# Display_EveryCook.net
KiCad netlist of a schematic drawn in EAGLE
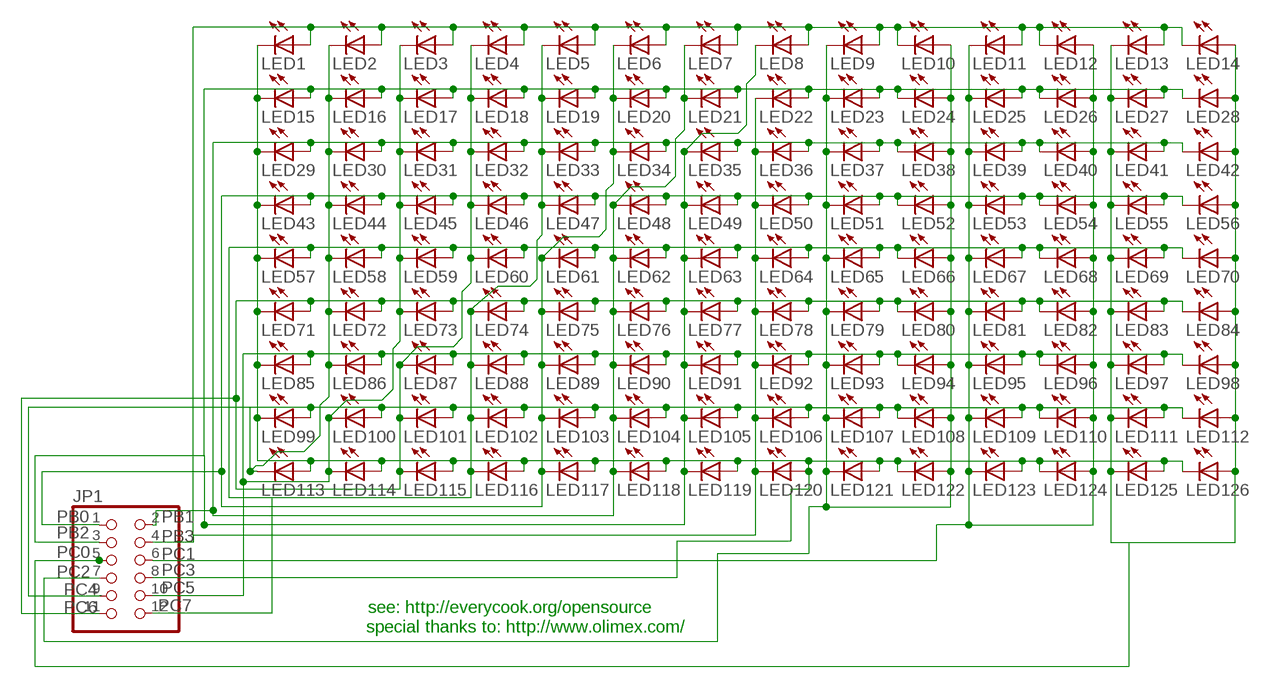
[diagram p0: schematic, sheet 1]

(export (version "E")
  (design (tool "Eeschema 10.0.6"))
  (components
    (comp (ref "JP1")
      (value "PINHD-2X6")
      (footprint "eagle-import:2X06")
      (libsource (lib "eagle-import") (part "PINHD-2X6"))
    )
    (comp (ref "LED1")
      (value "LEDKA-3528ASYC")
      (footprint "eagle-import:KA-3528ASYC")
      (libsource (lib "eagle-import") (part "LEDKA-3528ASYC"))
    )
    (comp (ref "LED2")
      (value "LEDKA-3528ASYC")
      (footprint "eagle-import:KA-3528ASYC")
      (libsource (lib "eagle-import") (part "LEDKA-3528ASYC"))
    )
    (comp (ref "LED3")
      (value "LEDKA-3528ASYC")
      (footprint "eagle-import:KA-3528ASYC")
      (libsource (lib "eagle-import") (part "LEDKA-3528ASYC"))
    )
    (comp (ref "LED4")
      (value "LEDKA-3528ASYC")
      (footprint "eagle-import:KA-3528ASYC")
      (libsource (lib "eagle-import") (part "LEDKA-3528ASYC"))
    )
    (comp (ref "LED5")
      (value "LEDKA-3528ASYC")
      (footprint "eagle-import:KA-3528ASYC")
      (libsource (lib "eagle-import") (part "LEDKA-3528ASYC"))
    )
    (comp (ref "LED6")
      (value "LEDKA-3528ASYC")
      (footprint "eagle-import:KA-3528ASYC")
      (libsource (lib "eagle-import") (part "LEDKA-3528ASYC"))
    )
    (comp (ref "LED7")
      (value "LEDKA-3528ASYC")
      (footprint "eagle-import:KA-3528ASYC")
      (libsource (lib "eagle-import") (part "LEDKA-3528ASYC"))
    )
    (comp (ref "LED8")
      (value "LEDKA-3528ASYC")
      (footprint "eagle-import:KA-3528ASYC")
      (libsource (lib "eagle-import") (part "LEDKA-3528ASYC"))
    )
    (comp (ref "LED9")
      (value "LEDKA-3528ASYC")
      (footprint "eagle-import:KA-3528ASYC")
      (libsource (lib "eagle-import") (part "LEDKA-3528ASYC"))
    )
    (comp (ref "LED10")
      (value "LEDKA-3528ASYC")
      (footprint "eagle-import:KA-3528ASYC")
      (libsource (lib "eagle-import") (part "LEDKA-3528ASYC"))
    )
    (comp (ref "LED11")
      (value "LEDKA-3528ASYC")
      (footprint "eagle-import:KA-3528ASYC")
      (libsource (lib "eagle-import") (part "LEDKA-3528ASYC"))
    )
    (comp (ref "LED12")
      (value "LEDKA-3528ASYC")
      (footprint "eagle-import:KA-3528ASYC")
      (libsource (lib "eagle-import") (part "LEDKA-3528ASYC"))
    )
    (comp (ref "LED13")
      (value "LEDKA-3528ASYC")
      (footprint "eagle-import:KA-3528ASYC")
      (libsource (lib "eagle-import") (part "LEDKA-3528ASYC"))
    )
    (comp (ref "LED14")
      (value "LEDKA-3528ASYC")
      (footprint "eagle-import:KA-3528ASYC")
      (libsource (lib "eagle-import") (part "LEDKA-3528ASYC"))
    )
    (comp (ref "LED15")
      (value "LEDKA-3528ASYC")
      (footprint "eagle-import:KA-3528ASYC")
      (libsource (lib "eagle-import") (part "LEDKA-3528ASYC"))
    )
    (comp (ref "LED16")
      (value "LEDKA-3528ASYC")
      (footprint "eagle-import:KA-3528ASYC")
      (libsource (lib "eagle-import") (part "LEDKA-3528ASYC"))
    )
    (comp (ref "LED17")
      (value "LEDKA-3528ASYC")
      (footprint "eagle-import:KA-3528ASYC")
      (libsource (lib "eagle-import") (part "LEDKA-3528ASYC"))
    )
    (comp (ref "LED18")
      (value "LEDKA-3528ASYC")
      (footprint "eagle-import:KA-3528ASYC")
      (libsource (lib "eagle-import") (part "LEDKA-3528ASYC"))
    )
    (comp (ref "LED19")
      (value "LEDKA-3528ASYC")
      (footprint "eagle-import:KA-3528ASYC")
      (libsource (lib "eagle-import") (part "LEDKA-3528ASYC"))
    )
    (comp (ref "LED20")
      (value "LEDKA-3528ASYC")
      (footprint "eagle-import:KA-3528ASYC")
      (libsource (lib "eagle-import") (part "LEDKA-3528ASYC"))
    )
    (comp (ref "LED21")
      (value "LEDKA-3528ASYC")
      (footprint "eagle-import:KA-3528ASYC")
      (libsource (lib "eagle-import") (part "LEDKA-3528ASYC"))
    )
    (comp (ref "LED22")
      (value "LEDKA-3528ASYC")
      (footprint "eagle-import:KA-3528ASYC")
      (libsource (lib "eagle-import") (part "LEDKA-3528ASYC"))
    )
    (comp (ref "LED23")
      (value "LEDKA-3528ASYC")
      (footprint "eagle-import:KA-3528ASYC")
      (libsource (lib "eagle-import") (part "LEDKA-3528ASYC"))
    )
    (comp (ref "LED24")
      (value "LEDKA-3528ASYC")
      (footprint "eagle-import:KA-3528ASYC")
      (libsource (lib "eagle-import") (part "LEDKA-3528ASYC"))
    )
    (comp (ref "LED25")
      (value "LEDKA-3528ASYC")
      (footprint "eagle-import:KA-3528ASYC")
      (libsource (lib "eagle-import") (part "LEDKA-3528ASYC"))
    )
    (comp (ref "LED26")
      (value "LEDKA-3528ASYC")
      (footprint "eagle-import:KA-3528ASYC")
      (libsource (lib "eagle-import") (part "LEDKA-3528ASYC"))
    )
    (comp (ref "LED27")
      (value "LEDKA-3528ASYC")
      (footprint "eagle-import:KA-3528ASYC")
      (libsource (lib "eagle-import") (part "LEDKA-3528ASYC"))
    )
    (comp (ref "LED28")
      (value "LEDKA-3528ASYC")
      (footprint "eagle-import:KA-3528ASYC")
      (libsource (lib "eagle-import") (part "LEDKA-3528ASYC"))
    )
    (comp (ref "LED29")
      (value "LEDKA-3528ASYC")
      (footprint "eagle-import:KA-3528ASYC")
      (libsource (lib "eagle-import") (part "LEDKA-3528ASYC"))
    )
    (comp (ref "LED30")
      (value "LEDKA-3528ASYC")
      (footprint "eagle-import:KA-3528ASYC")
      (libsource (lib "eagle-import") (part "LEDKA-3528ASYC"))
    )
    (comp (ref "LED31")
      (value "LEDKA-3528ASYC")
      (footprint "eagle-import:KA-3528ASYC")
      (libsource (lib "eagle-import") (part "LEDKA-3528ASYC"))
    )
    (comp (ref "LED32")
      (value "LEDKA-3528ASYC")
      (footprint "eagle-import:KA-3528ASYC")
      (libsource (lib "eagle-import") (part "LEDKA-3528ASYC"))
    )
    (comp (ref "LED33")
      (value "LEDKA-3528ASYC")
      (footprint "eagle-import:KA-3528ASYC")
      (libsource (lib "eagle-import") (part "LEDKA-3528ASYC"))
    )
    (comp (ref "LED34")
      (value "LEDKA-3528ASYC")
      (footprint "eagle-import:KA-3528ASYC")
      (libsource (lib "eagle-import") (part "LEDKA-3528ASYC"))
    )
    (comp (ref "LED35")
      (value "LEDKA-3528ASYC")
      (footprint "eagle-import:KA-3528ASYC")
      (libsource (lib "eagle-import") (part "LEDKA-3528ASYC"))
    )
    (comp (ref "LED36")
      (value "LEDKA-3528ASYC")
      (footprint "eagle-import:KA-3528ASYC")
      (libsource (lib "eagle-import") (part "LEDKA-3528ASYC"))
    )
    (comp (ref "LED37")
      (value "LEDKA-3528ASYC")
      (footprint "eagle-import:KA-3528ASYC")
      (libsource (lib "eagle-import") (part "LEDKA-3528ASYC"))
    )
    (comp (ref "LED38")
      (value "LEDKA-3528ASYC")
      (footprint "eagle-import:KA-3528ASYC")
      (libsource (lib "eagle-import") (part "LEDKA-3528ASYC"))
    )
    (comp (ref "LED39")
      (value "LEDKA-3528ASYC")
      (footprint "eagle-import:KA-3528ASYC")
      (libsource (lib "eagle-import") (part "LEDKA-3528ASYC"))
    )
    (comp (ref "LED40")
      (value "LEDKA-3528ASYC")
      (footprint "eagle-import:KA-3528ASYC")
      (libsource (lib "eagle-import") (part "LEDKA-3528ASYC"))
    )
    (comp (ref "LED41")
      (value "LEDKA-3528ASYC")
      (footprint "eagle-import:KA-3528ASYC")
      (libsource (lib "eagle-import") (part "LEDKA-3528ASYC"))
    )
    (comp (ref "LED42")
      (value "LEDKA-3528ASYC")
      (footprint "eagle-import:KA-3528ASYC")
      (libsource (lib "eagle-import") (part "LEDKA-3528ASYC"))
    )
    (comp (ref "LED43")
      (value "LEDKA-3528ASYC")
      (footprint "eagle-import:KA-3528ASYC")
      (libsource (lib "eagle-import") (part "LEDKA-3528ASYC"))
    )
    (comp (ref "LED44")
      (value "LEDKA-3528ASYC")
      (footprint "eagle-import:KA-3528ASYC")
      (libsource (lib "eagle-import") (part "LEDKA-3528ASYC"))
    )
    (comp (ref "LED45")
      (value "LEDKA-3528ASYC")
      (footprint "eagle-import:KA-3528ASYC")
      (libsource (lib "eagle-import") (part "LEDKA-3528ASYC"))
    )
    (comp (ref "LED46")
      (value "LEDKA-3528ASYC")
      (footprint "eagle-import:KA-3528ASYC")
      (libsource (lib "eagle-import") (part "LEDKA-3528ASYC"))
    )
    (comp (ref "LED47")
      (value "LEDKA-3528ASYC")
      (footprint "eagle-import:KA-3528ASYC")
      (libsource (lib "eagle-import") (part "LEDKA-3528ASYC"))
    )
    (comp (ref "LED48")
      (value "LEDKA-3528ASYC")
      (footprint "eagle-import:KA-3528ASYC")
      (libsource (lib "eagle-import") (part "LEDKA-3528ASYC"))
    )
    (comp (ref "LED49")
      (value "LEDKA-3528ASYC")
      (footprint "eagle-import:KA-3528ASYC")
      (libsource (lib "eagle-import") (part "LEDKA-3528ASYC"))
    )
    (comp (ref "LED50")
      (value "LEDKA-3528ASYC")
      (footprint "eagle-import:KA-3528ASYC")
      (libsource (lib "eagle-import") (part "LEDKA-3528ASYC"))
    )
    (comp (ref "LED51")
      (value "LEDKA-3528ASYC")
      (footprint "eagle-import:KA-3528ASYC")
      (libsource (lib "eagle-import") (part "LEDKA-3528ASYC"))
    )
    (comp (ref "LED52")
      (value "LEDKA-3528ASYC")
      (footprint "eagle-import:KA-3528ASYC")
      (libsource (lib "eagle-import") (part "LEDKA-3528ASYC"))
    )
    (comp (ref "LED53")
      (value "LEDKA-3528ASYC")
      (footprint "eagle-import:KA-3528ASYC")
      (libsource (lib "eagle-import") (part "LEDKA-3528ASYC"))
    )
    (comp (ref "LED54")
      (value "LEDKA-3528ASYC")
      (footprint "eagle-import:KA-3528ASYC")
      (libsource (lib "eagle-import") (part "LEDKA-3528ASYC"))
    )
    (comp (ref "LED55")
      (value "LEDKA-3528ASYC")
      (footprint "eagle-import:KA-3528ASYC")
      (libsource (lib "eagle-import") (part "LEDKA-3528ASYC"))
    )
    (comp (ref "LED56")
      (value "LEDKA-3528ASYC")
      (footprint "eagle-import:KA-3528ASYC")
      (libsource (lib "eagle-import") (part "LEDKA-3528ASYC"))
    )
    (comp (ref "LED57")
      (value "LEDKA-3528ASYC")
      (footprint "eagle-import:KA-3528ASYC")
      (libsource (lib "eagle-import") (part "LEDKA-3528ASYC"))
    )
    (comp (ref "LED58")
      (value "LEDKA-3528ASYC")
      (footprint "eagle-import:KA-3528ASYC")
      (libsource (lib "eagle-import") (part "LEDKA-3528ASYC"))
    )
    (comp (ref "LED59")
      (value "LEDKA-3528ASYC")
      (footprint "eagle-import:KA-3528ASYC")
      (libsource (lib "eagle-import") (part "LEDKA-3528ASYC"))
    )
    (comp (ref "LED60")
      (value "LEDKA-3528ASYC")
      (footprint "eagle-import:KA-3528ASYC")
      (libsource (lib "eagle-import") (part "LEDKA-3528ASYC"))
    )
    (comp (ref "LED61")
      (value "LEDKA-3528ASYC")
      (footprint "eagle-import:KA-3528ASYC")
      (libsource (lib "eagle-import") (part "LEDKA-3528ASYC"))
    )
    (comp (ref "LED62")
      (value "LEDKA-3528ASYC")
      (footprint "eagle-import:KA-3528ASYC")
      (libsource (lib "eagle-import") (part "LEDKA-3528ASYC"))
    )
    (comp (ref "LED63")
      (value "LEDKA-3528ASYC")
      (footprint "eagle-import:KA-3528ASYC")
      (libsource (lib "eagle-import") (part "LEDKA-3528ASYC"))
    )
    (comp (ref "LED64")
      (value "LEDKA-3528ASYC")
      (footprint "eagle-import:KA-3528ASYC")
      (libsource (lib "eagle-import") (part "LEDKA-3528ASYC"))
    )
    (comp (ref "LED65")
      (value "LEDKA-3528ASYC")
      (footprint "eagle-import:KA-3528ASYC")
      (libsource (lib "eagle-import") (part "LEDKA-3528ASYC"))
    )
    (comp (ref "LED66")
      (value "LEDKA-3528ASYC")
      (footprint "eagle-import:KA-3528ASYC")
      (libsource (lib "eagle-import") (part "LEDKA-3528ASYC"))
    )
    (comp (ref "LED67")
      (value "LEDKA-3528ASYC")
      (footprint "eagle-import:KA-3528ASYC")
      (libsource (lib "eagle-import") (part "LEDKA-3528ASYC"))
    )
    (comp (ref "LED68")
      (value "LEDKA-3528ASYC")
      (footprint "eagle-import:KA-3528ASYC")
      (libsource (lib "eagle-import") (part "LEDKA-3528ASYC"))
    )
    (comp (ref "LED69")
      (value "LEDKA-3528ASYC")
      (footprint "eagle-import:KA-3528ASYC")
      (libsource (lib "eagle-import") (part "LEDKA-3528ASYC"))
    )
    (comp (ref "LED70")
      (value "LEDKA-3528ASYC")
      (footprint "eagle-import:KA-3528ASYC")
      (libsource (lib "eagle-import") (part "LEDKA-3528ASYC"))
    )
    (comp (ref "LED71")
      (value "LEDKA-3528ASYC")
      (footprint "eagle-import:KA-3528ASYC")
      (libsource (lib "eagle-import") (part "LEDKA-3528ASYC"))
    )
    (comp (ref "LED72")
      (value "LEDKA-3528ASYC")
      (footprint "eagle-import:KA-3528ASYC")
      (libsource (lib "eagle-import") (part "LEDKA-3528ASYC"))
    )
    (comp (ref "LED73")
      (value "LEDKA-3528ASYC")
      (footprint "eagle-import:KA-3528ASYC")
      (libsource (lib "eagle-import") (part "LEDKA-3528ASYC"))
    )
    (comp (ref "LED74")
      (value "LEDKA-3528ASYC")
      (footprint "eagle-import:KA-3528ASYC")
      (libsource (lib "eagle-import") (part "LEDKA-3528ASYC"))
    )
    (comp (ref "LED75")
      (value "LEDKA-3528ASYC")
      (footprint "eagle-import:KA-3528ASYC")
      (libsource (lib "eagle-import") (part "LEDKA-3528ASYC"))
    )
    (comp (ref "LED76")
      (value "LEDKA-3528ASYC")
      (footprint "eagle-import:KA-3528ASYC")
      (libsource (lib "eagle-import") (part "LEDKA-3528ASYC"))
    )
    (comp (ref "LED77")
      (value "LEDKA-3528ASYC")
      (footprint "eagle-import:KA-3528ASYC")
      (libsource (lib "eagle-import") (part "LEDKA-3528ASYC"))
    )
    (comp (ref "LED78")
      (value "LEDKA-3528ASYC")
      (footprint "eagle-import:KA-3528ASYC")
      (libsource (lib "eagle-import") (part "LEDKA-3528ASYC"))
    )
    (comp (ref "LED79")
      (value "LEDKA-3528ASYC")
      (footprint "eagle-import:KA-3528ASYC")
      (libsource (lib "eagle-import") (part "LEDKA-3528ASYC"))
    )
    (comp (ref "LED80")
      (value "LEDKA-3528ASYC")
      (footprint "eagle-import:KA-3528ASYC")
      (libsource (lib "eagle-import") (part "LEDKA-3528ASYC"))
    )
    (comp (ref "LED81")
      (value "LEDKA-3528ASYC")
      (footprint "eagle-import:KA-3528ASYC")
      (libsource (lib "eagle-import") (part "LEDKA-3528ASYC"))
    )
    (comp (ref "LED82")
      (value "LEDKA-3528ASYC")
      (footprint "eagle-import:KA-3528ASYC")
      (libsource (lib "eagle-import") (part "LEDKA-3528ASYC"))
    )
    (comp (ref "LED83")
      (value "LEDKA-3528ASYC")
      (footprint "eagle-import:KA-3528ASYC")
      (libsource (lib "eagle-import") (part "LEDKA-3528ASYC"))
    )
    (comp (ref "LED84")
      (value "LEDKA-3528ASYC")
      (footprint "eagle-import:KA-3528ASYC")
      (libsource (lib "eagle-import") (part "LEDKA-3528ASYC"))
    )
    (comp (ref "LED85")
      (value "LEDKA-3528ASYC")
      (footprint "eagle-import:KA-3528ASYC")
      (libsource (lib "eagle-import") (part "LEDKA-3528ASYC"))
    )
    (comp (ref "LED86")
      (value "LEDKA-3528ASYC")
      (footprint "eagle-import:KA-3528ASYC")
      (libsource (lib "eagle-import") (part "LEDKA-3528ASYC"))
    )
    (comp (ref "LED87")
      (value "LEDKA-3528ASYC")
      (footprint "eagle-import:KA-3528ASYC")
      (libsource (lib "eagle-import") (part "LEDKA-3528ASYC"))
    )
    (comp (ref "LED88")
      (value "LEDKA-3528ASYC")
      (footprint "eagle-import:KA-3528ASYC")
      (libsource (lib "eagle-import") (part "LEDKA-3528ASYC"))
    )
    (comp (ref "LED89")
      (value "LEDKA-3528ASYC")
      (footprint "eagle-import:KA-3528ASYC")
      (libsource (lib "eagle-import") (part "LEDKA-3528ASYC"))
    )
    (comp (ref "LED90")
      (value "LEDKA-3528ASYC")
      (footprint "eagle-import:KA-3528ASYC")
      (libsource (lib "eagle-import") (part "LEDKA-3528ASYC"))
    )
    (comp (ref "LED91")
      (value "LEDKA-3528ASYC")
      (footprint "eagle-import:KA-3528ASYC")
      (libsource (lib "eagle-import") (part "LEDKA-3528ASYC"))
    )
    (comp (ref "LED92")
      (value "LEDKA-3528ASYC")
      (footprint "eagle-import:KA-3528ASYC")
      (libsource (lib "eagle-import") (part "LEDKA-3528ASYC"))
    )
    (comp (ref "LED93")
      (value "LEDKA-3528ASYC")
      (footprint "eagle-import:KA-3528ASYC")
      (libsource (lib "eagle-import") (part "LEDKA-3528ASYC"))
    )
    (comp (ref "LED94")
      (value "LEDKA-3528ASYC")
      (footprint "eagle-import:KA-3528ASYC")
      (libsource (lib "eagle-import") (part "LEDKA-3528ASYC"))
    )
    (comp (ref "LED95")
      (value "LEDKA-3528ASYC")
      (footprint "eagle-import:KA-3528ASYC")
      (libsource (lib "eagle-import") (part "LEDKA-3528ASYC"))
    )
    (comp (ref "LED96")
      (value "LEDKA-3528ASYC")
      (footprint "eagle-import:KA-3528ASYC")
      (libsource (lib "eagle-import") (part "LEDKA-3528ASYC"))
    )
    (comp (ref "LED97")
      (value "LEDKA-3528ASYC")
      (footprint "eagle-import:KA-3528ASYC")
      (libsource (lib "eagle-import") (part "LEDKA-3528ASYC"))
    )
    (comp (ref "LED98")
      (value "LEDKA-3528ASYC")
      (footprint "eagle-import:KA-3528ASYC")
      (libsource (lib "eagle-import") (part "LEDKA-3528ASYC"))
    )
    (comp (ref "LED99")
      (value "LEDKA-3528ASYC")
      (footprint "eagle-import:KA-3528ASYC")
      (libsource (lib "eagle-import") (part "LEDKA-3528ASYC"))
    )
    (comp (ref "LED100")
      (value "LEDKA-3528ASYC")
      (footprint "eagle-import:KA-3528ASYC")
      (libsource (lib "eagle-import") (part "LEDKA-3528ASYC"))
    )
    (comp (ref "LED101")
      (value "LEDKA-3528ASYC")
      (footprint "eagle-import:KA-3528ASYC")
      (libsource (lib "eagle-import") (part "LEDKA-3528ASYC"))
    )
    (comp (ref "LED102")
      (value "LEDKA-3528ASYC")
      (footprint "eagle-import:KA-3528ASYC")
      (libsource (lib "eagle-import") (part "LEDKA-3528ASYC"))
    )
    (comp (ref "LED103")
      (value "LEDKA-3528ASYC")
      (footprint "eagle-import:KA-3528ASYC")
      (libsource (lib "eagle-import") (part "LEDKA-3528ASYC"))
    )
    (comp (ref "LED104")
      (value "LEDKA-3528ASYC")
      (footprint "eagle-import:KA-3528ASYC")
      (libsource (lib "eagle-import") (part "LEDKA-3528ASYC"))
    )
    (comp (ref "LED105")
      (value "LEDKA-3528ASYC")
      (footprint "eagle-import:KA-3528ASYC")
      (libsource (lib "eagle-import") (part "LEDKA-3528ASYC"))
    )
    (comp (ref "LED106")
      (value "LEDKA-3528ASYC")
      (footprint "eagle-import:KA-3528ASYC")
      (libsource (lib "eagle-import") (part "LEDKA-3528ASYC"))
    )
    (comp (ref "LED107")
      (value "LEDKA-3528ASYC")
      (footprint "eagle-import:KA-3528ASYC")
      (libsource (lib "eagle-import") (part "LEDKA-3528ASYC"))
    )
    (comp (ref "LED108")
      (value "LEDKA-3528ASYC")
      (footprint "eagle-import:KA-3528ASYC")
      (libsource (lib "eagle-import") (part "LEDKA-3528ASYC"))
    )
    (comp (ref "LED109")
      (value "LEDKA-3528ASYC")
      (footprint "eagle-import:KA-3528ASYC")
      (libsource (lib "eagle-import") (part "LEDKA-3528ASYC"))
    )
    (comp (ref "LED110")
      (value "LEDKA-3528ASYC")
      (footprint "eagle-import:KA-3528ASYC")
      (libsource (lib "eagle-import") (part "LEDKA-3528ASYC"))
    )
    (comp (ref "LED111")
      (value "LEDKA-3528ASYC")
      (footprint "eagle-import:KA-3528ASYC")
      (libsource (lib "eagle-import") (part "LEDKA-3528ASYC"))
    )
    (comp (ref "LED112")
      (value "LEDKA-3528ASYC")
      (footprint "eagle-import:KA-3528ASYC")
      (libsource (lib "eagle-import") (part "LEDKA-3528ASYC"))
    )
    (comp (ref "LED113")
      (value "LEDKA-3528ASYC")
      (footprint "eagle-import:KA-3528ASYC")
      (libsource (lib "eagle-import") (part "LEDKA-3528ASYC"))
    )
    (comp (ref "LED114")
      (value "LEDKA-3528ASYC")
      (footprint "eagle-import:KA-3528ASYC")
      (libsource (lib "eagle-import") (part "LEDKA-3528ASYC"))
    )
    (comp (ref "LED115")
      (value "LEDKA-3528ASYC")
      (footprint "eagle-import:KA-3528ASYC")
      (libsource (lib "eagle-import") (part "LEDKA-3528ASYC"))
    )
    (comp (ref "LED116")
      (value "LEDKA-3528ASYC")
      (footprint "eagle-import:KA-3528ASYC")
      (libsource (lib "eagle-import") (part "LEDKA-3528ASYC"))
    )
    (comp (ref "LED117")
      (value "LEDKA-3528ASYC")
      (footprint "eagle-import:KA-3528ASYC")
      (libsource (lib "eagle-import") (part "LEDKA-3528ASYC"))
    )
    (comp (ref "LED118")
      (value "LEDKA-3528ASYC")
      (footprint "eagle-import:KA-3528ASYC")
      (libsource (lib "eagle-import") (part "LEDKA-3528ASYC"))
    )
    (comp (ref "LED119")
      (value "LEDKA-3528ASYC")
      (footprint "eagle-import:KA-3528ASYC")
      (libsource (lib "eagle-import") (part "LEDKA-3528ASYC"))
    )
    (comp (ref "LED120")
      (value "LEDKA-3528ASYC")
      (footprint "eagle-import:KA-3528ASYC")
      (libsource (lib "eagle-import") (part "LEDKA-3528ASYC"))
    )
    (comp (ref "LED121")
      (value "LEDKA-3528ASYC")
      (footprint "eagle-import:KA-3528ASYC")
      (libsource (lib "eagle-import") (part "LEDKA-3528ASYC"))
    )
    (comp (ref "LED122")
      (value "LEDKA-3528ASYC")
      (footprint "eagle-import:KA-3528ASYC")
      (libsource (lib "eagle-import") (part "LEDKA-3528ASYC"))
    )
    (comp (ref "LED123")
      (value "LEDKA-3528ASYC")
      (footprint "eagle-import:KA-3528ASYC")
      (libsource (lib "eagle-import") (part "LEDKA-3528ASYC"))
    )
    (comp (ref "LED124")
      (value "LEDKA-3528ASYC")
      (footprint "eagle-import:KA-3528ASYC")
      (libsource (lib "eagle-import") (part "LEDKA-3528ASYC"))
    )
    (comp (ref "LED125")
      (value "LEDKA-3528ASYC")
      (footprint "eagle-import:KA-3528ASYC")
      (libsource (lib "eagle-import") (part "LEDKA-3528ASYC"))
    )
    (comp (ref "LED126")
      (value "LEDKA-3528ASYC")
      (footprint "eagle-import:KA-3528ASYC")
      (libsource (lib "eagle-import") (part "LEDKA-3528ASYC"))
    )
  )
  (nets
    (net (code "1") (name "/PB0") (class "Default")
      (node (ref "JP1") (pin "1") (pinfunction "1_1") (pintype "passive"))
      (node (ref "LED103") (pin "C") (pinfunction "C_C") (pintype "passive"))
      (node (ref "LED117") (pin "C") (pinfunction "C_C") (pintype "passive"))
      (node (ref "LED20") (pin "C") (pinfunction "C_C") (pintype "passive"))
      (node (ref "LED34") (pin "C") (pinfunction "C_C") (pintype "passive"))
      (node (ref "LED43") (pin "A") (pinfunction "A_A") (pintype "passive"))
      (node (ref "LED44") (pin "A") (pinfunction "A_A") (pintype "passive"))
      (node (ref "LED45") (pin "A") (pinfunction "A_A") (pintype "passive"))
      (node (ref "LED46") (pin "A") (pinfunction "A_A") (pintype "passive"))
      (node (ref "LED47") (pin "A") (pinfunction "A_A") (pintype "passive"))
      (node (ref "LED48") (pin "A") (pinfunction "A_A") (pintype "passive"))
      (node (ref "LED49") (pin "A") (pinfunction "A_A") (pintype "passive"))
      (node (ref "LED50") (pin "A") (pinfunction "A_A") (pintype "passive"))
      (node (ref "LED51") (pin "A") (pinfunction "A_A") (pintype "passive"))
      (node (ref "LED52") (pin "C") (pinfunction "C_C") (pintype "passive"))
      (node (ref "LED53") (pin "A") (pinfunction "A_A") (pintype "passive"))
      (node (ref "LED54") (pin "C") (pinfunction "C_C") (pintype "passive"))
      (node (ref "LED55") (pin "A") (pinfunction "A_A") (pintype "passive"))
      (node (ref "LED56") (pin "C") (pinfunction "C_C") (pintype "passive"))
      (node (ref "LED6") (pin "C") (pinfunction "C_C") (pintype "passive"))
      (node (ref "LED61") (pin "C") (pinfunction "C_C") (pintype "passive"))
      (node (ref "LED75") (pin "C") (pinfunction "C_C") (pintype "passive"))
      (node (ref "LED89") (pin "C") (pinfunction "C_C") (pintype "passive"))
    )
    (net (code "2") (name "/PB1") (class "Default")
      (node (ref "JP1") (pin "2") (pinfunction "2_2") (pintype "passive"))
      (node (ref "LED104") (pin "C") (pinfunction "C_C") (pintype "passive"))
      (node (ref "LED118") (pin "C") (pinfunction "C_C") (pintype "passive"))
      (node (ref "LED21") (pin "C") (pinfunction "C_C") (pintype "passive"))
      (node (ref "LED29") (pin "A") (pinfunction "A_A") (pintype "passive"))
      (node (ref "LED30") (pin "A") (pinfunction "A_A") (pintype "passive"))
      (node (ref "LED31") (pin "A") (pinfunction "A_A") (pintype "passive"))
      (node (ref "LED32") (pin "A") (pinfunction "A_A") (pintype "passive"))
      (node (ref "LED33") (pin "A") (pinfunction "A_A") (pintype "passive"))
      (node (ref "LED34") (pin "A") (pinfunction "A_A") (pintype "passive"))
      (node (ref "LED35") (pin "A") (pinfunction "A_A") (pintype "passive"))
      (node (ref "LED36") (pin "A") (pinfunction "A_A") (pintype "passive"))
      (node (ref "LED37") (pin "A") (pinfunction "A_A") (pintype "passive"))
      (node (ref "LED38") (pin "C") (pinfunction "C_C") (pintype "passive"))
      (node (ref "LED39") (pin "A") (pinfunction "A_A") (pintype "passive"))
      (node (ref "LED40") (pin "C") (pinfunction "C_C") (pintype "passive"))
      (node (ref "LED41") (pin "A") (pinfunction "A_A") (pintype "passive"))
      (node (ref "LED42") (pin "C") (pinfunction "C_C") (pintype "passive"))
      (node (ref "LED48") (pin "C") (pinfunction "C_C") (pintype "passive"))
      (node (ref "LED62") (pin "C") (pinfunction "C_C") (pintype "passive"))
      (node (ref "LED7") (pin "C") (pinfunction "C_C") (pintype "passive"))
      (node (ref "LED76") (pin "C") (pinfunction "C_C") (pintype "passive"))
      (node (ref "LED90") (pin "C") (pinfunction "C_C") (pintype "passive"))
    )
    (net (code "3") (name "/PB2") (class "Default")
      (node (ref "JP1") (pin "3") (pinfunction "3_3") (pintype "passive"))
      (node (ref "LED105") (pin "C") (pinfunction "C_C") (pintype "passive"))
      (node (ref "LED119") (pin "C") (pinfunction "C_C") (pintype "passive"))
      (node (ref "LED15") (pin "A") (pinfunction "A_A") (pintype "passive"))
      (node (ref "LED16") (pin "A") (pinfunction "A_A") (pintype "passive"))
      (node (ref "LED17") (pin "A") (pinfunction "A_A") (pintype "passive"))
      (node (ref "LED18") (pin "A") (pinfunction "A_A") (pintype "passive"))
      (node (ref "LED19") (pin "A") (pinfunction "A_A") (pintype "passive"))
      (node (ref "LED20") (pin "A") (pinfunction "A_A") (pintype "passive"))
      (node (ref "LED21") (pin "A") (pinfunction "A_A") (pintype "passive"))
      (node (ref "LED22") (pin "A") (pinfunction "A_A") (pintype "passive"))
      (node (ref "LED23") (pin "A") (pinfunction "A_A") (pintype "passive"))
      (node (ref "LED24") (pin "C") (pinfunction "C_C") (pintype "passive"))
      (node (ref "LED25") (pin "A") (pinfunction "A_A") (pintype "passive"))
      (node (ref "LED26") (pin "C") (pinfunction "C_C") (pintype "passive"))
      (node (ref "LED27") (pin "A") (pinfunction "A_A") (pintype "passive"))
      (node (ref "LED28") (pin "C") (pinfunction "C_C") (pintype "passive"))
      (node (ref "LED35") (pin "C") (pinfunction "C_C") (pintype "passive"))
      (node (ref "LED49") (pin "C") (pinfunction "C_C") (pintype "passive"))
      (node (ref "LED63") (pin "C") (pinfunction "C_C") (pintype "passive"))
      (node (ref "LED77") (pin "C") (pinfunction "C_C") (pintype "passive"))
      (node (ref "LED8") (pin "C") (pinfunction "C_C") (pintype "passive"))
      (node (ref "LED91") (pin "C") (pinfunction "C_C") (pintype "passive"))
    )
    (net (code "4") (name "/PB3") (class "Default")
      (node (ref "JP1") (pin "4") (pinfunction "4_4") (pintype "passive"))
      (node (ref "LED1") (pin "A") (pinfunction "A_A") (pintype "passive"))
      (node (ref "LED10") (pin "C") (pinfunction "C_C") (pintype "passive"))
      (node (ref "LED106") (pin "C") (pinfunction "C_C") (pintype "passive"))
      (node (ref "LED11") (pin "A") (pinfunction "A_A") (pintype "passive"))
      (node (ref "LED12") (pin "C") (pinfunction "C_C") (pintype "passive"))
      (node (ref "LED120") (pin "C") (pinfunction "C_C") (pintype "passive"))
      (node (ref "LED13") (pin "A") (pinfunction "A_A") (pintype "passive"))
      (node (ref "LED14") (pin "C") (pinfunction "C_C") (pintype "passive"))
      (node (ref "LED2") (pin "A") (pinfunction "A_A") (pintype "passive"))
      (node (ref "LED22") (pin "C") (pinfunction "C_C") (pintype "passive"))
      (node (ref "LED3") (pin "A") (pinfunction "A_A") (pintype "passive"))
      (node (ref "LED36") (pin "C") (pinfunction "C_C") (pintype "passive"))
      (node (ref "LED4") (pin "A") (pinfunction "A_A") (pintype "passive"))
      (node (ref "LED5") (pin "A") (pinfunction "A_A") (pintype "passive"))
      (node (ref "LED50") (pin "C") (pinfunction "C_C") (pintype "passive"))
      (node (ref "LED6") (pin "A") (pinfunction "A_A") (pintype "passive"))
      (node (ref "LED64") (pin "C") (pinfunction "C_C") (pintype "passive"))
      (node (ref "LED7") (pin "A") (pinfunction "A_A") (pintype "passive"))
      (node (ref "LED78") (pin "C") (pinfunction "C_C") (pintype "passive"))
      (node (ref "LED8") (pin "A") (pinfunction "A_A") (pintype "passive"))
      (node (ref "LED9") (pin "A") (pinfunction "A_A") (pintype "passive"))
      (node (ref "LED92") (pin "C") (pinfunction "C_C") (pintype "passive"))
    )
    (net (code "5") (name "/PC0") (class "Default")
      (node (ref "JP1") (pin "5") (pinfunction "5_5") (pintype "passive"))
      (node (ref "LED111") (pin "C") (pinfunction "C_C") (pintype "passive"))
      (node (ref "LED112") (pin "A") (pinfunction "A_A") (pintype "passive"))
      (node (ref "LED125") (pin "C") (pinfunction "C_C") (pintype "passive"))
      (node (ref "LED126") (pin "A") (pinfunction "A_A") (pintype "passive"))
      (node (ref "LED13") (pin "C") (pinfunction "C_C") (pintype "passive"))
      (node (ref "LED14") (pin "A") (pinfunction "A_A") (pintype "passive"))
      (node (ref "LED27") (pin "C") (pinfunction "C_C") (pintype "passive"))
      (node (ref "LED28") (pin "A") (pinfunction "A_A") (pintype "passive"))
      (node (ref "LED41") (pin "C") (pinfunction "C_C") (pintype "passive"))
      (node (ref "LED42") (pin "A") (pinfunction "A_A") (pintype "passive"))
      (node (ref "LED55") (pin "C") (pinfunction "C_C") (pintype "passive"))
      (node (ref "LED56") (pin "A") (pinfunction "A_A") (pintype "passive"))
      (node (ref "LED69") (pin "C") (pinfunction "C_C") (pintype "passive"))
      (node (ref "LED70") (pin "A") (pinfunction "A_A") (pintype "passive"))
      (node (ref "LED83") (pin "C") (pinfunction "C_C") (pintype "passive"))
      (node (ref "LED84") (pin "A") (pinfunction "A_A") (pintype "passive"))
      (node (ref "LED97") (pin "C") (pinfunction "C_C") (pintype "passive"))
      (node (ref "LED98") (pin "A") (pinfunction "A_A") (pintype "passive"))
    )
    (net (code "6") (name "/PC1") (class "Default")
      (node (ref "JP1") (pin "6") (pinfunction "6_6") (pintype "passive"))
      (node (ref "LED109") (pin "C") (pinfunction "C_C") (pintype "passive"))
      (node (ref "LED11") (pin "C") (pinfunction "C_C") (pintype "passive"))
      (node (ref "LED110") (pin "A") (pinfunction "A_A") (pintype "passive"))
      (node (ref "LED12") (pin "A") (pinfunction "A_A") (pintype "passive"))
      (node (ref "LED123") (pin "C") (pinfunction "C_C") (pintype "passive"))
      (node (ref "LED124") (pin "A") (pinfunction "A_A") (pintype "passive"))
      (node (ref "LED25") (pin "C") (pinfunction "C_C") (pintype "passive"))
      (node (ref "LED26") (pin "A") (pinfunction "A_A") (pintype "passive"))
      (node (ref "LED39") (pin "C") (pinfunction "C_C") (pintype "passive"))
      (node (ref "LED40") (pin "A") (pinfunction "A_A") (pintype "passive"))
      (node (ref "LED53") (pin "C") (pinfunction "C_C") (pintype "passive"))
      (node (ref "LED54") (pin "A") (pinfunction "A_A") (pintype "passive"))
      (node (ref "LED67") (pin "C") (pinfunction "C_C") (pintype "passive"))
      (node (ref "LED68") (pin "A") (pinfunction "A_A") (pintype "passive"))
      (node (ref "LED81") (pin "C") (pinfunction "C_C") (pintype "passive"))
      (node (ref "LED82") (pin "A") (pinfunction "A_A") (pintype "passive"))
      (node (ref "LED95") (pin "C") (pinfunction "C_C") (pintype "passive"))
      (node (ref "LED96") (pin "A") (pinfunction "A_A") (pintype "passive"))
    )
    (net (code "7") (name "/PC2") (class "Default")
      (node (ref "JP1") (pin "7") (pinfunction "7_7") (pintype "passive"))
      (node (ref "LED10") (pin "A") (pinfunction "A_A") (pintype "passive"))
      (node (ref "LED107") (pin "C") (pinfunction "C_C") (pintype "passive"))
      (node (ref "LED108") (pin "A") (pinfunction "A_A") (pintype "passive"))
      (node (ref "LED121") (pin "C") (pinfunction "C_C") (pintype "passive"))
      (node (ref "LED122") (pin "A") (pinfunction "A_A") (pintype "passive"))
      (node (ref "LED23") (pin "C") (pinfunction "C_C") (pintype "passive"))
      (node (ref "LED24") (pin "A") (pinfunction "A_A") (pintype "passive"))
      (node (ref "LED37") (pin "C") (pinfunction "C_C") (pintype "passive"))
      (node (ref "LED38") (pin "A") (pinfunction "A_A") (pintype "passive"))
      (node (ref "LED51") (pin "C") (pinfunction "C_C") (pintype "passive"))
      (node (ref "LED52") (pin "A") (pinfunction "A_A") (pintype "passive"))
      (node (ref "LED65") (pin "C") (pinfunction "C_C") (pintype "passive"))
      (node (ref "LED66") (pin "A") (pinfunction "A_A") (pintype "passive"))
      (node (ref "LED79") (pin "C") (pinfunction "C_C") (pintype "passive"))
      (node (ref "LED80") (pin "A") (pinfunction "A_A") (pintype "passive"))
      (node (ref "LED9") (pin "C") (pinfunction "C_C") (pintype "passive"))
      (node (ref "LED93") (pin "C") (pinfunction "C_C") (pintype "passive"))
      (node (ref "LED94") (pin "A") (pinfunction "A_A") (pintype "passive"))
    )
    (net (code "8") (name "/PC3") (class "Default")
      (node (ref "JP1") (pin "8") (pinfunction "8_8") (pintype "passive"))
      (node (ref "LED1") (pin "C") (pinfunction "C_C") (pintype "passive"))
      (node (ref "LED113") (pin "A") (pinfunction "A_A") (pintype "passive"))
      (node (ref "LED114") (pin "A") (pinfunction "A_A") (pintype "passive"))
      (node (ref "LED115") (pin "A") (pinfunction "A_A") (pintype "passive"))
      (node (ref "LED116") (pin "A") (pinfunction "A_A") (pintype "passive"))
      (node (ref "LED117") (pin "A") (pinfunction "A_A") (pintype "passive"))
      (node (ref "LED118") (pin "A") (pinfunction "A_A") (pintype "passive"))
      (node (ref "LED119") (pin "A") (pinfunction "A_A") (pintype "passive"))
      (node (ref "LED120") (pin "A") (pinfunction "A_A") (pintype "passive"))
      (node (ref "LED121") (pin "A") (pinfunction "A_A") (pintype "passive"))
      (node (ref "LED122") (pin "C") (pinfunction "C_C") (pintype "passive"))
      (node (ref "LED123") (pin "A") (pinfunction "A_A") (pintype "passive"))
      (node (ref "LED124") (pin "C") (pinfunction "C_C") (pintype "passive"))
      (node (ref "LED125") (pin "A") (pinfunction "A_A") (pintype "passive"))
      (node (ref "LED126") (pin "C") (pinfunction "C_C") (pintype "passive"))
      (node (ref "LED15") (pin "C") (pinfunction "C_C") (pintype "passive"))
      (node (ref "LED29") (pin "C") (pinfunction "C_C") (pintype "passive"))
      (node (ref "LED43") (pin "C") (pinfunction "C_C") (pintype "passive"))
      (node (ref "LED57") (pin "C") (pinfunction "C_C") (pintype "passive"))
      (node (ref "LED71") (pin "C") (pinfunction "C_C") (pintype "passive"))
      (node (ref "LED85") (pin "C") (pinfunction "C_C") (pintype "passive"))
      (node (ref "LED99") (pin "C") (pinfunction "C_C") (pintype "passive"))
    )
    (net (code "9") (name "/PC4") (class "Default")
      (node (ref "JP1") (pin "9") (pinfunction "9_9") (pintype "passive"))
      (node (ref "LED100") (pin "A") (pinfunction "A_A") (pintype "passive"))
      (node (ref "LED101") (pin "A") (pinfunction "A_A") (pintype "passive"))
      (node (ref "LED102") (pin "A") (pinfunction "A_A") (pintype "passive"))
      (node (ref "LED103") (pin "A") (pinfunction "A_A") (pintype "passive"))
      (node (ref "LED104") (pin "A") (pinfunction "A_A") (pintype "passive"))
      (node (ref "LED105") (pin "A") (pinfunction "A_A") (pintype "passive"))
      (node (ref "LED106") (pin "A") (pinfunction "A_A") (pintype "passive"))
      (node (ref "LED107") (pin "A") (pinfunction "A_A") (pintype "passive"))
      (node (ref "LED108") (pin "C") (pinfunction "C_C") (pintype "passive"))
      (node (ref "LED109") (pin "A") (pinfunction "A_A") (pintype "passive"))
      (node (ref "LED110") (pin "C") (pinfunction "C_C") (pintype "passive"))
      (node (ref "LED111") (pin "A") (pinfunction "A_A") (pintype "passive"))
      (node (ref "LED112") (pin "C") (pinfunction "C_C") (pintype "passive"))
      (node (ref "LED113") (pin "C") (pinfunction "C_C") (pintype "passive"))
      (node (ref "LED16") (pin "C") (pinfunction "C_C") (pintype "passive"))
      (node (ref "LED2") (pin "C") (pinfunction "C_C") (pintype "passive"))
      (node (ref "LED30") (pin "C") (pinfunction "C_C") (pintype "passive"))
      (node (ref "LED44") (pin "C") (pinfunction "C_C") (pintype "passive"))
      (node (ref "LED58") (pin "C") (pinfunction "C_C") (pintype "passive"))
      (node (ref "LED72") (pin "C") (pinfunction "C_C") (pintype "passive"))
      (node (ref "LED86") (pin "C") (pinfunction "C_C") (pintype "passive"))
      (node (ref "LED99") (pin "A") (pinfunction "A_A") (pintype "passive"))
    )
    (net (code "10") (name "/PC5") (class "Default")
      (node (ref "JP1") (pin "10") (pinfunction "10_10") (pintype "passive"))
      (node (ref "LED100") (pin "C") (pinfunction "C_C") (pintype "passive"))
      (node (ref "LED114") (pin "C") (pinfunction "C_C") (pintype "passive"))
      (node (ref "LED17") (pin "C") (pinfunction "C_C") (pintype "passive"))
      (node (ref "LED3") (pin "C") (pinfunction "C_C") (pintype "passive"))
      (node (ref "LED31") (pin "C") (pinfunction "C_C") (pintype "passive"))
      (node (ref "LED45") (pin "C") (pinfunction "C_C") (pintype "passive"))
      (node (ref "LED59") (pin "C") (pinfunction "C_C") (pintype "passive"))
      (node (ref "LED73") (pin "C") (pinfunction "C_C") (pintype "passive"))
      (node (ref "LED85") (pin "A") (pinfunction "A_A") (pintype "passive"))
      (node (ref "LED86") (pin "A") (pinfunction "A_A") (pintype "passive"))
      (node (ref "LED87") (pin "A") (pinfunction "A_A") (pintype "passive"))
      (node (ref "LED88") (pin "A") (pinfunction "A_A") (pintype "passive"))
      (node (ref "LED89") (pin "A") (pinfunction "A_A") (pintype "passive"))
      (node (ref "LED90") (pin "A") (pinfunction "A_A") (pintype "passive"))
      (node (ref "LED91") (pin "A") (pinfunction "A_A") (pintype "passive"))
      (node (ref "LED92") (pin "A") (pinfunction "A_A") (pintype "passive"))
      (node (ref "LED93") (pin "A") (pinfunction "A_A") (pintype "passive"))
      (node (ref "LED94") (pin "C") (pinfunction "C_C") (pintype "passive"))
      (node (ref "LED95") (pin "A") (pinfunction "A_A") (pintype "passive"))
      (node (ref "LED96") (pin "C") (pinfunction "C_C") (pintype "passive"))
      (node (ref "LED97") (pin "A") (pinfunction "A_A") (pintype "passive"))
      (node (ref "LED98") (pin "C") (pinfunction "C_C") (pintype "passive"))
    )
    (net (code "11") (name "/PC6") (class "Default")
      (node (ref "JP1") (pin "11") (pinfunction "11_11") (pintype "passive"))
      (node (ref "LED101") (pin "C") (pinfunction "C_C") (pintype "passive"))
      (node (ref "LED115") (pin "C") (pinfunction "C_C") (pintype "passive"))
      (node (ref "LED18") (pin "C") (pinfunction "C_C") (pintype "passive"))
      (node (ref "LED32") (pin "C") (pinfunction "C_C") (pintype "passive"))
      (node (ref "LED4") (pin "C") (pinfunction "C_C") (pintype "passive"))
      (node (ref "LED46") (pin "C") (pinfunction "C_C") (pintype "passive"))
      (node (ref "LED60") (pin "C") (pinfunction "C_C") (pintype "passive"))
      (node (ref "LED71") (pin "A") (pinfunction "A_A") (pintype "passive"))
      (node (ref "LED72") (pin "A") (pinfunction "A_A") (pintype "passive"))
      (node (ref "LED73") (pin "A") (pinfunction "A_A") (pintype "passive"))
      (node (ref "LED74") (pin "A") (pinfunction "A_A") (pintype "passive"))
      (node (ref "LED75") (pin "A") (pinfunction "A_A") (pintype "passive"))
      (node (ref "LED76") (pin "A") (pinfunction "A_A") (pintype "passive"))
      (node (ref "LED77") (pin "A") (pinfunction "A_A") (pintype "passive"))
      (node (ref "LED78") (pin "A") (pinfunction "A_A") (pintype "passive"))
      (node (ref "LED79") (pin "A") (pinfunction "A_A") (pintype "passive"))
      (node (ref "LED80") (pin "C") (pinfunction "C_C") (pintype "passive"))
      (node (ref "LED81") (pin "A") (pinfunction "A_A") (pintype "passive"))
      (node (ref "LED82") (pin "C") (pinfunction "C_C") (pintype "passive"))
      (node (ref "LED83") (pin "A") (pinfunction "A_A") (pintype "passive"))
      (node (ref "LED84") (pin "C") (pinfunction "C_C") (pintype "passive"))
      (node (ref "LED87") (pin "C") (pinfunction "C_C") (pintype "passive"))
    )
    (net (code "12") (name "/PC7") (class "Default")
      (node (ref "JP1") (pin "12") (pinfunction "12_12") (pintype "passive"))
      (node (ref "LED102") (pin "C") (pinfunction "C_C") (pintype "passive"))
      (node (ref "LED116") (pin "C") (pinfunction "C_C") (pintype "passive"))
      (node (ref "LED19") (pin "C") (pinfunction "C_C") (pintype "passive"))
      (node (ref "LED33") (pin "C") (pinfunction "C_C") (pintype "passive"))
      (node (ref "LED47") (pin "C") (pinfunction "C_C") (pintype "passive"))
      (node (ref "LED5") (pin "C") (pinfunction "C_C") (pintype "passive"))
      (node (ref "LED57") (pin "A") (pinfunction "A_A") (pintype "passive"))
      (node (ref "LED58") (pin "A") (pinfunction "A_A") (pintype "passive"))
      (node (ref "LED59") (pin "A") (pinfunction "A_A") (pintype "passive"))
      (node (ref "LED60") (pin "A") (pinfunction "A_A") (pintype "passive"))
      (node (ref "LED61") (pin "A") (pinfunction "A_A") (pintype "passive"))
      (node (ref "LED62") (pin "A") (pinfunction "A_A") (pintype "passive"))
      (node (ref "LED63") (pin "A") (pinfunction "A_A") (pintype "passive"))
      (node (ref "LED64") (pin "A") (pinfunction "A_A") (pintype "passive"))
      (node (ref "LED65") (pin "A") (pinfunction "A_A") (pintype "passive"))
      (node (ref "LED66") (pin "C") (pinfunction "C_C") (pintype "passive"))
      (node (ref "LED67") (pin "A") (pinfunction "A_A") (pintype "passive"))
      (node (ref "LED68") (pin "C") (pinfunction "C_C") (pintype "passive"))
      (node (ref "LED69") (pin "A") (pinfunction "A_A") (pintype "passive"))
      (node (ref "LED70") (pin "C") (pinfunction "C_C") (pintype "passive"))
      (node (ref "LED74") (pin "C") (pinfunction "C_C") (pintype "passive"))
      (node (ref "LED88") (pin "C") (pinfunction "C_C") (pintype "passive"))
    )
  )
)
